# EstufaIOT.net
KiCad netlist of a schematic drawn in EAGLE
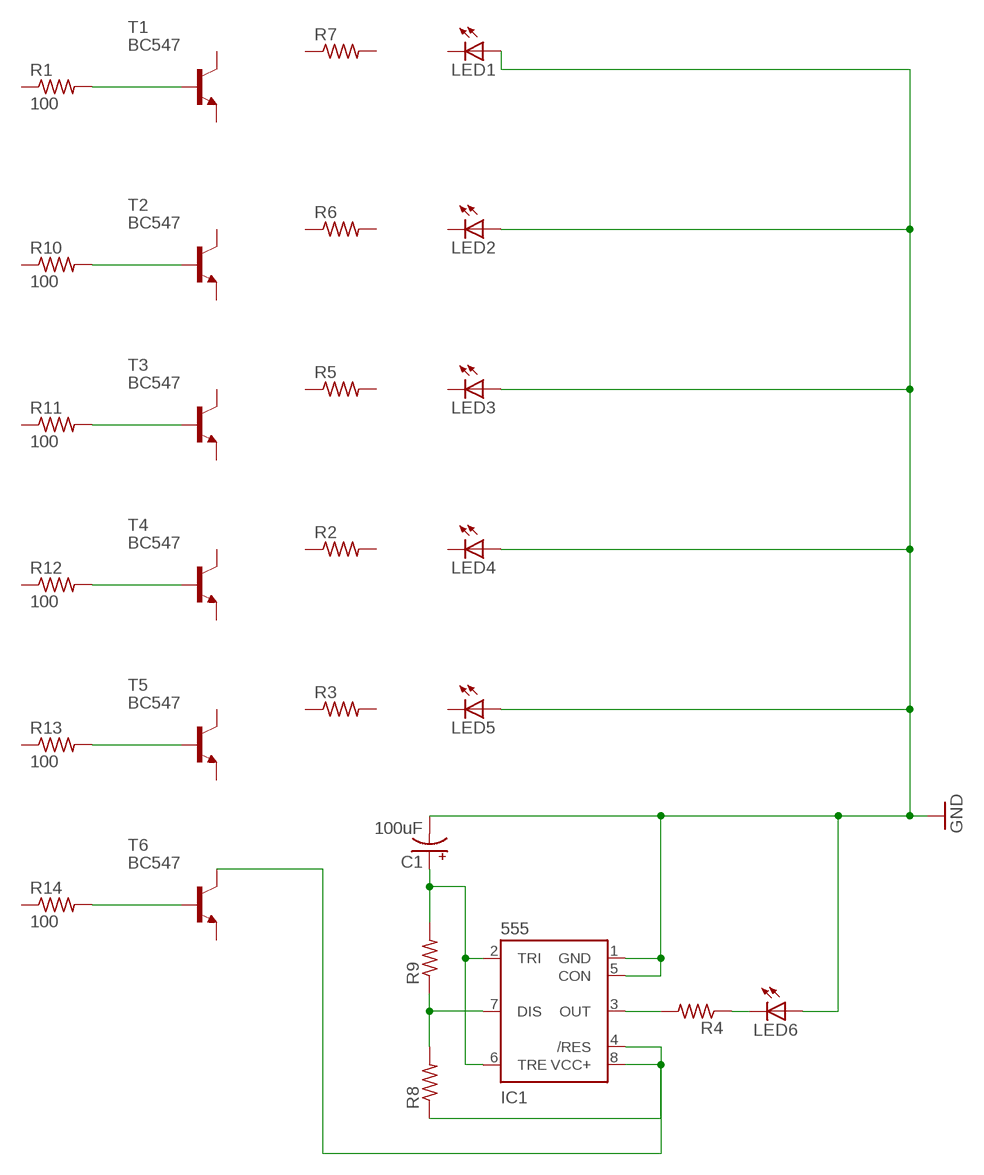
[diagram p0: schematic, sheet 1]

(export (version "E")
  (design (tool "Eeschema 10.0.6"))
  (components
    (comp (ref "C1")
      (value "100uF")
      (footprint "eagle-import:CPOL-RADIAL-2.5MM-6.5MM")
      (libsource (lib "eagle-import") (part "100UF-POLAR-RADIAL-2.5MM-25V-20%"))
    )
    (comp (ref "IC1")
      (value "555")
      (footprint "eagle-import:SO08")
      (libsource (lib "eagle-import") (part "555D"))
    )
    (comp (ref "LED1")
      (value "LED5MM")
      (footprint "eagle-import:LED5MM")
      (libsource (lib "eagle-import") (part "LED5MM"))
    )
    (comp (ref "LED2")
      (value "LED5MM")
      (footprint "eagle-import:LED5MM")
      (libsource (lib "eagle-import") (part "LED5MM"))
    )
    (comp (ref "LED3")
      (value "LED5MM")
      (footprint "eagle-import:LED5MM")
      (libsource (lib "eagle-import") (part "LED5MM"))
    )
    (comp (ref "LED4")
      (value "LED5MM")
      (footprint "eagle-import:LED5MM")
      (libsource (lib "eagle-import") (part "LED5MM"))
    )
    (comp (ref "LED5")
      (value "LED5MM")
      (footprint "eagle-import:LED5MM")
      (libsource (lib "eagle-import") (part "LED5MM"))
    )
    (comp (ref "LED6")
      (value "LED5MM")
      (footprint "eagle-import:LED5MM")
      (libsource (lib "eagle-import") (part "LED5MM"))
    )
    (comp (ref "R1")
      (value "100")
      (footprint "eagle-import:0805-THM")
      (libsource (lib "eagle-import") (part "FLIPFLOP-RES"))
    )
    (comp (ref "R2")
      (value "FLIPFLOP-RES")
      (footprint "eagle-import:0805-THM")
      (libsource (lib "eagle-import") (part "FLIPFLOP-RES"))
    )
    (comp (ref "R3")
      (value "FLIPFLOP-RES")
      (footprint "eagle-import:0805-THM")
      (libsource (lib "eagle-import") (part "FLIPFLOP-RES"))
    )
    (comp (ref "R4")
      (value "FLIPFLOP-RES")
      (footprint "eagle-import:0805-THM")
      (libsource (lib "eagle-import") (part "FLIPFLOP-RES"))
    )
    (comp (ref "R5")
      (value "FLIPFLOP-RES")
      (footprint "eagle-import:0805-THM")
      (libsource (lib "eagle-import") (part "FLIPFLOP-RES"))
    )
    (comp (ref "R6")
      (value "FLIPFLOP-RES")
      (footprint "eagle-import:0805-THM")
      (libsource (lib "eagle-import") (part "FLIPFLOP-RES"))
    )
    (comp (ref "R7")
      (value "FLIPFLOP-RES")
      (footprint "eagle-import:0805-THM")
      (libsource (lib "eagle-import") (part "FLIPFLOP-RES"))
    )
    (comp (ref "R8")
      (value "FLIPFLOP-RES")
      (footprint "eagle-import:0805-THM")
      (libsource (lib "eagle-import") (part "FLIPFLOP-RES"))
    )
    (comp (ref "R9")
      (value "FLIPFLOP-RES")
      (footprint "eagle-import:0805-THM")
      (libsource (lib "eagle-import") (part "FLIPFLOP-RES"))
    )
    (comp (ref "R10")
      (value "100")
      (footprint "eagle-import:0805-THM")
      (libsource (lib "eagle-import") (part "FLIPFLOP-RES"))
    )
    (comp (ref "R11")
      (value "100")
      (footprint "eagle-import:0805-THM")
      (libsource (lib "eagle-import") (part "FLIPFLOP-RES"))
    )
    (comp (ref "R12")
      (value "100")
      (footprint "eagle-import:0805-THM")
      (libsource (lib "eagle-import") (part "FLIPFLOP-RES"))
    )
    (comp (ref "R13")
      (value "100")
      (footprint "eagle-import:0805-THM")
      (libsource (lib "eagle-import") (part "FLIPFLOP-RES"))
    )
    (comp (ref "R14")
      (value "100")
      (footprint "eagle-import:0805-THM")
      (libsource (lib "eagle-import") (part "FLIPFLOP-RES"))
    )
    (comp (ref "T1")
      (value "BC547")
      (footprint "eagle-import:TO92")
      (libsource (lib "eagle-import") (part "BC547"))
    )
    (comp (ref "T2")
      (value "BC547")
      (footprint "eagle-import:TO92")
      (libsource (lib "eagle-import") (part "BC547"))
    )
    (comp (ref "T3")
      (value "BC547")
      (footprint "eagle-import:TO92")
      (libsource (lib "eagle-import") (part "BC547"))
    )
    (comp (ref "T4")
      (value "BC547")
      (footprint "eagle-import:TO92")
      (libsource (lib "eagle-import") (part "BC547"))
    )
    (comp (ref "T5")
      (value "BC547")
      (footprint "eagle-import:TO92")
      (libsource (lib "eagle-import") (part "BC547"))
    )
    (comp (ref "T6")
      (value "BC547")
      (footprint "eagle-import:TO92")
      (libsource (lib "eagle-import") (part "BC547"))
    )
  )
  (nets
    (net (code "1") (name "GND") (class "Default")
      (node (ref "C1") (pin "2") (pinfunction "-_2") (pintype "passive"))
      (node (ref "IC1") (pin "1") (pinfunction "GND_1") (pintype "power_in"))
      (node (ref "IC1") (pin "5") (pinfunction "CON_5") (pintype "input"))
      (node (ref "LED1") (pin "A") (pinfunction "A_A") (pintype "passive"))
      (node (ref "LED2") (pin "A") (pinfunction "A_A") (pintype "passive"))
      (node (ref "LED3") (pin "A") (pinfunction "A_A") (pintype "passive"))
      (node (ref "LED4") (pin "A") (pinfunction "A_A") (pintype "passive"))
      (node (ref "LED5") (pin "A") (pinfunction "A_A") (pintype "passive"))
      (node (ref "LED6") (pin "A") (pinfunction "A_A") (pintype "passive"))
    )
    (net (code "2") (name "Net-(C1-+)") (class "Default")
      (node (ref "C1") (pin "1") (pinfunction "+_1") (pintype "passive"))
      (node (ref "IC1") (pin "2") (pinfunction "TRI_2") (pintype "input"))
      (node (ref "IC1") (pin "6") (pinfunction "TRE_6") (pintype "input"))
      (node (ref "R9") (pin "2") (pinfunction "2_2") (pintype "passive"))
    )
    (net (code "3") (name "Net-(IC1-DIS)") (class "Default")
      (node (ref "IC1") (pin "7") (pinfunction "DIS_7") (pintype "input"))
      (node (ref "R8") (pin "2") (pinfunction "2_2") (pintype "passive"))
      (node (ref "R9") (pin "1") (pinfunction "1_1") (pintype "passive"))
    )
    (net (code "4") (name "Net-(IC1-OUT)") (class "Default")
      (node (ref "IC1") (pin "3") (pinfunction "OUT_3") (pintype "output"))
      (node (ref "R4") (pin "2") (pinfunction "2_2") (pintype "passive"))
    )
    (net (code "5") (name "Net-(IC1-VCC+)") (class "Default")
      (node (ref "IC1") (pin "4") (pinfunction "/RES_4") (pintype "input"))
      (node (ref "IC1") (pin "8") (pinfunction "VCC+_8") (pintype "power_in"))
      (node (ref "R8") (pin "1") (pinfunction "1_1") (pintype "passive"))
      (node (ref "T6") (pin "3") (pinfunction "C_3") (pintype "passive"))
    )
    (net (code "6") (name "Net-(LED6-C)") (class "Default")
      (node (ref "LED6") (pin "K") (pinfunction "C_K") (pintype "passive"))
      (node (ref "R4") (pin "1") (pinfunction "1_1") (pintype "passive"))
    )
    (net (code "7") (name "Net-(T1-B)") (class "Default")
      (node (ref "R1") (pin "2") (pinfunction "2_2") (pintype "passive"))
      (node (ref "T1") (pin "2") (pinfunction "B_2") (pintype "passive"))
    )
    (net (code "8") (name "Net-(T2-B)") (class "Default")
      (node (ref "R10") (pin "2") (pinfunction "2_2") (pintype "passive"))
      (node (ref "T2") (pin "2") (pinfunction "B_2") (pintype "passive"))
    )
    (net (code "9") (name "Net-(T3-B)") (class "Default")
      (node (ref "R11") (pin "2") (pinfunction "2_2") (pintype "passive"))
      (node (ref "T3") (pin "2") (pinfunction "B_2") (pintype "passive"))
    )
    (net (code "10") (name "Net-(T4-B)") (class "Default")
      (node (ref "R12") (pin "2") (pinfunction "2_2") (pintype "passive"))
      (node (ref "T4") (pin "2") (pinfunction "B_2") (pintype "passive"))
    )
    (net (code "11") (name "Net-(T5-B)") (class "Default")
      (node (ref "R13") (pin "2") (pinfunction "2_2") (pintype "passive"))
      (node (ref "T5") (pin "2") (pinfunction "B_2") (pintype "passive"))
    )
    (net (code "12") (name "Net-(T6-B)") (class "Default")
      (node (ref "R14") (pin "2") (pinfunction "2_2") (pintype "passive"))
      (node (ref "T6") (pin "2") (pinfunction "B_2") (pintype "passive"))
    )
    (net (code "13") (name "unconnected-(LED1-C-PadK)") (class "Default")
      (node (ref "LED1") (pin "K") (pinfunction "C_K") (pintype "passive"))
    )
    (net (code "14") (name "unconnected-(LED2-C-PadK)") (class "Default")
      (node (ref "LED2") (pin "K") (pinfunction "C_K") (pintype "passive"))
    )
    (net (code "15") (name "unconnected-(LED3-C-PadK)") (class "Default")
      (node (ref "LED3") (pin "K") (pinfunction "C_K") (pintype "passive"))
    )
    (net (code "16") (name "unconnected-(LED4-C-PadK)") (class "Default")
      (node (ref "LED4") (pin "K") (pinfunction "C_K") (pintype "passive"))
    )
    (net (code "17") (name "unconnected-(LED5-C-PadK)") (class "Default")
      (node (ref "LED5") (pin "K") (pinfunction "C_K") (pintype "passive"))
    )
    (net (code "18") (name "unconnected-(R1-Pad1)") (class "Default")
      (node (ref "R1") (pin "1") (pinfunction "1_1") (pintype "passive"))
    )
    (net (code "19") (name "unconnected-(R2-Pad1)") (class "Default")
      (node (ref "R2") (pin "1") (pinfunction "1_1") (pintype "passive"))
    )
    (net (code "20") (name "unconnected-(R2-Pad2)") (class "Default")
      (node (ref "R2") (pin "2") (pinfunction "2_2") (pintype "passive"))
    )
    (net (code "21") (name "unconnected-(R3-Pad1)") (class "Default")
      (node (ref "R3") (pin "1") (pinfunction "1_1") (pintype "passive"))
    )
    (net (code "22") (name "unconnected-(R3-Pad2)") (class "Default")
      (node (ref "R3") (pin "2") (pinfunction "2_2") (pintype "passive"))
    )
    (net (code "23") (name "unconnected-(R5-Pad1)") (class "Default")
      (node (ref "R5") (pin "1") (pinfunction "1_1") (pintype "passive"))
    )
    (net (code "24") (name "unconnected-(R5-Pad2)") (class "Default")
      (node (ref "R5") (pin "2") (pinfunction "2_2") (pintype "passive"))
    )
    (net (code "25") (name "unconnected-(R6-Pad1)") (class "Default")
      (node (ref "R6") (pin "1") (pinfunction "1_1") (pintype "passive"))
    )
    (net (code "26") (name "unconnected-(R6-Pad2)") (class "Default")
      (node (ref "R6") (pin "2") (pinfunction "2_2") (pintype "passive"))
    )
    (net (code "27") (name "unconnected-(R7-Pad1)") (class "Default")
      (node (ref "R7") (pin "1") (pinfunction "1_1") (pintype "passive"))
    )
    (net (code "28") (name "unconnected-(R7-Pad2)") (class "Default")
      (node (ref "R7") (pin "2") (pinfunction "2_2") (pintype "passive"))
    )
    (net (code "29") (name "unconnected-(R10-Pad1)") (class "Default")
      (node (ref "R10") (pin "1") (pinfunction "1_1") (pintype "passive"))
    )
    (net (code "30") (name "unconnected-(R11-Pad1)") (class "Default")
      (node (ref "R11") (pin "1") (pinfunction "1_1") (pintype "passive"))
    )
    (net (code "31") (name "unconnected-(R12-Pad1)") (class "Default")
      (node (ref "R12") (pin "1") (pinfunction "1_1") (pintype "passive"))
    )
    (net (code "32") (name "unconnected-(R13-Pad1)") (class "Default")
      (node (ref "R13") (pin "1") (pinfunction "1_1") (pintype "passive"))
    )
    (net (code "33") (name "unconnected-(R14-Pad1)") (class "Default")
      (node (ref "R14") (pin "1") (pinfunction "1_1") (pintype "passive"))
    )
    (net (code "34") (name "unconnected-(T1-C-Pad3)") (class "Default")
      (node (ref "T1") (pin "3") (pinfunction "C_3") (pintype "passive"))
    )
    (net (code "35") (name "unconnected-(T1-E-Pad1)") (class "Default")
      (node (ref "T1") (pin "1") (pinfunction "E_1") (pintype "passive"))
    )
    (net (code "36") (name "unconnected-(T2-C-Pad3)") (class "Default")
      (node (ref "T2") (pin "3") (pinfunction "C_3") (pintype "passive"))
    )
    (net (code "37") (name "unconnected-(T2-E-Pad1)") (class "Default")
      (node (ref "T2") (pin "1") (pinfunction "E_1") (pintype "passive"))
    )
    (net (code "38") (name "unconnected-(T3-C-Pad3)") (class "Default")
      (node (ref "T3") (pin "3") (pinfunction "C_3") (pintype "passive"))
    )
    (net (code "39") (name "unconnected-(T3-E-Pad1)") (class "Default")
      (node (ref "T3") (pin "1") (pinfunction "E_1") (pintype "passive"))
    )
    (net (code "40") (name "unconnected-(T4-C-Pad3)") (class "Default")
      (node (ref "T4") (pin "3") (pinfunction "C_3") (pintype "passive"))
    )
    (net (code "41") (name "unconnected-(T4-E-Pad1)") (class "Default")
      (node (ref "T4") (pin "1") (pinfunction "E_1") (pintype "passive"))
    )
    (net (code "42") (name "unconnected-(T5-C-Pad3)") (class "Default")
      (node (ref "T5") (pin "3") (pinfunction "C_3") (pintype "passive"))
    )
    (net (code "43") (name "unconnected-(T5-E-Pad1)") (class "Default")
      (node (ref "T5") (pin "1") (pinfunction "E_1") (pintype "passive"))
    )
    (net (code "44") (name "unconnected-(T6-E-Pad1)") (class "Default")
      (node (ref "T6") (pin "1") (pinfunction "E_1") (pintype "passive"))
    )
  )
)
